# 06-NOTStatusLed.net
KiCad netlist of a schematic drawn in Altium Designer
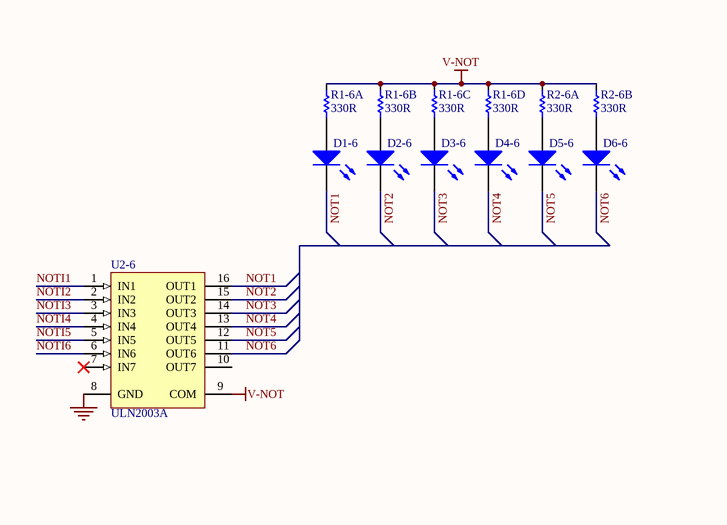
[diagram p0: 06-NOTStatusLed.SchDoc, left]
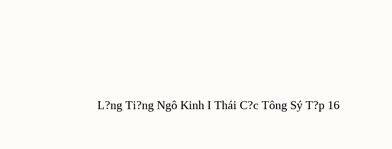
[diagram p1: 06-NOTStatusLed.SchDoc, right]

(export (version "E")
  (design (tool "Eeschema 10.0.6"))
  (components
    (comp (ref "D1-6")
      (value "LED")
      (footprint "LED-0805")
      (description "Typical RED, GREEN, YELLOW, AMBER GaAs LED")
      (fields (field (name "PUBLISHER") "Altium Limited"))
      (libsource (lib "Miscellaneous Devices") (part "LED2"))
    )
    (comp (ref "D2-6")
      (value "LED")
      (footprint "LED-0805")
      (description "Typical RED, GREEN, YELLOW, AMBER GaAs LED")
      (fields (field (name "PUBLISHER") "Altium Limited"))
      (libsource (lib "Miscellaneous Devices") (part "LED2"))
    )
    (comp (ref "D3-6")
      (value "LED")
      (footprint "LED-0805")
      (description "Typical RED, GREEN, YELLOW, AMBER GaAs LED")
      (fields (field (name "PUBLISHER") "Altium Limited"))
      (libsource (lib "Miscellaneous Devices") (part "LED2"))
    )
    (comp (ref "D4-6")
      (value "LED")
      (footprint "LED-0805")
      (description "Typical RED, GREEN, YELLOW, AMBER GaAs LED")
      (fields (field (name "PUBLISHER") "Altium Limited"))
      (libsource (lib "Miscellaneous Devices") (part "LED2"))
    )
    (comp (ref "D5-6")
      (value "LED")
      (footprint "LED-0805")
      (description "Typical RED, GREEN, YELLOW, AMBER GaAs LED")
      (fields (field (name "PUBLISHER") "Altium Limited"))
      (libsource (lib "Miscellaneous Devices") (part "LED2"))
    )
    (comp (ref "D6-6")
      (value "LED")
      (footprint "LED-0805")
      (description "Typical RED, GREEN, YELLOW, AMBER GaAs LED")
      (fields (field (name "PUBLISHER") "Altium Limited"))
      (libsource (lib "Miscellaneous Devices") (part "LED2"))
    )
    (comp (ref "R1-6")
      (value "330R")
      (footprint "R-Array-0603-4")
      (description "RES ARRAY 4 RES 330 OHM 1206")
      (fields
        (field (name "DIGI-KEY PART NUMBER") "Y9331TR-ND")
        (field (name "MANUFACTURER") "Panasonic Electronic Components")
      )
      (libsource (lib "Dlib") (part "Res Array 4"))
    )
    (comp (ref "R2-6")
      (value "330R")
      (footprint "R-Array-0603-4")
      (description "RES ARRAY 4 RES 330 OHM 1206")
      (fields
        (field (name "DIGI-KEY PART NUMBER") "Y9331TR-ND")
        (field (name "MANUFACTURER") "Panasonic Electronic Components")
      )
      (libsource (lib "Dlib") (part "Res Array 4"))
    )
    (comp (ref "U2-6")
      (value "ULN2003A")
      (footprint "SOIC-16")
      (description "High-Voltage, High-Current Darlington Array")
      (fields (field (name "PUBLISHER") "Altium Limited"))
      (libsource (lib "Allegro Interface Darlington Driver") (part "ULN2003A"))
    )
  )
  (nets
    (net (code "1") (name "/NOT1") (class "Default")
      (node (ref "D1-6") (pin "2") (pinfunction "K_2") (pintype "passive"))
      (node (ref "U2-6") (pin "16") (pinfunction "OUT1_16") (pintype "open_collector"))
    )
    (net (code "2") (name "/NOT2") (class "Default")
      (node (ref "D2-6") (pin "2") (pinfunction "K_2") (pintype "passive"))
      (node (ref "U2-6") (pin "15") (pinfunction "OUT2_15") (pintype "open_collector"))
    )
    (net (code "3") (name "/NOT3") (class "Default")
      (node (ref "D3-6") (pin "2") (pinfunction "K_2") (pintype "passive"))
      (node (ref "U2-6") (pin "14") (pinfunction "OUT3_14") (pintype "open_collector"))
    )
    (net (code "4") (name "/NOT4") (class "Default")
      (node (ref "D4-6") (pin "2") (pinfunction "K_2") (pintype "passive"))
      (node (ref "U2-6") (pin "13") (pinfunction "OUT4_13") (pintype "open_collector"))
    )
    (net (code "5") (name "/NOT5") (class "Default")
      (node (ref "D5-6") (pin "2") (pinfunction "K_2") (pintype "passive"))
      (node (ref "U2-6") (pin "12") (pinfunction "OUT5_12") (pintype "open_collector"))
    )
    (net (code "6") (name "/NOT6") (class "Default")
      (node (ref "D6-6") (pin "2") (pinfunction "K_2") (pintype "passive"))
      (node (ref "U2-6") (pin "11") (pinfunction "OUT6_11") (pintype "open_collector"))
    )
    (net (code "7") (name "/NOTI1") (class "Default")
      (node (ref "U2-6") (pin "1") (pinfunction "IN1_1") (pintype "input"))
    )
    (net (code "8") (name "/NOTI2") (class "Default")
      (node (ref "U2-6") (pin "2") (pinfunction "IN2_2") (pintype "input"))
    )
    (net (code "9") (name "/NOTI3") (class "Default")
      (node (ref "U2-6") (pin "3") (pinfunction "IN3_3") (pintype "input"))
    )
    (net (code "10") (name "/NOTI4") (class "Default")
      (node (ref "U2-6") (pin "4") (pinfunction "IN4_4") (pintype "input"))
    )
    (net (code "11") (name "/NOTI5") (class "Default")
      (node (ref "U2-6") (pin "5") (pinfunction "IN5_5") (pintype "input"))
    )
    (net (code "12") (name "/NOTI6") (class "Default")
      (node (ref "U2-6") (pin "6") (pinfunction "IN6_6") (pintype "input"))
    )
    (net (code "13") (name "GND") (class "Default")
      (node (ref "U2-6") (pin "8") (pinfunction "GND_8") (pintype "power_in"))
    )
    (net (code "14") (name "Net-(D1-6-A)") (class "Default")
      (node (ref "D1-6") (pin "1") (pinfunction "A_1") (pintype "passive"))
      (node (ref "R1-6") (pin "1") (pinfunction "1_1") (pintype "passive"))
    )
    (net (code "15") (name "Net-(D2-6-A)") (class "Default")
      (node (ref "D2-6") (pin "1") (pinfunction "A_1") (pintype "passive"))
      (node (ref "R1-6") (pin "3") (pinfunction "1_3") (pintype "passive"))
    )
    (net (code "16") (name "Net-(D3-6-A)") (class "Default")
      (node (ref "D3-6") (pin "1") (pinfunction "A_1") (pintype "passive"))
      (node (ref "R1-6") (pin "5") (pinfunction "1_5") (pintype "passive"))
    )
    (net (code "17") (name "Net-(D4-6-A)") (class "Default")
      (node (ref "D4-6") (pin "1") (pinfunction "A_1") (pintype "passive"))
      (node (ref "R1-6") (pin "7") (pinfunction "1_7") (pintype "passive"))
    )
    (net (code "18") (name "Net-(D5-6-A)") (class "Default")
      (node (ref "D5-6") (pin "1") (pinfunction "A_1") (pintype "passive"))
      (node (ref "R2-6") (pin "1") (pinfunction "1_1") (pintype "passive"))
    )
    (net (code "19") (name "Net-(D6-6-A)") (class "Default")
      (node (ref "D6-6") (pin "1") (pinfunction "A_1") (pintype "passive"))
      (node (ref "R2-6") (pin "3") (pinfunction "1_3") (pintype "passive"))
    )
    (net (code "20") (name "V-NOT") (class "Default")
      (node (ref "R1-6") (pin "2") (pinfunction "2_2") (pintype "passive"))
      (node (ref "R1-6") (pin "4") (pinfunction "2_4") (pintype "passive"))
      (node (ref "R1-6") (pin "6") (pinfunction "2_6") (pintype "passive"))
      (node (ref "R1-6") (pin "8") (pinfunction "2_8") (pintype "passive"))
      (node (ref "R2-6") (pin "2") (pinfunction "2_2") (pintype "passive"))
      (node (ref "R2-6") (pin "4") (pinfunction "2_4") (pintype "passive"))
      (node (ref "U2-6") (pin "9") (pinfunction "COM_9") (pintype "passive"))
    )
    (net (code "21") (name "unconnected-(U2-6-IN7-Pad7)") (class "Default")
      (node (ref "U2-6") (pin "7") (pinfunction "IN7_7") (pintype "input+no_connect"))
    )
    (net (code "22") (name "unconnected-(U2-6-OUT7-Pad10)") (class "Default")
      (node (ref "U2-6") (pin "10") (pinfunction "OUT7_10") (pintype "open_collector"))
    )
  )
)
